# MAX3232.net
KiCad netlist of a schematic drawn in Altium Designer
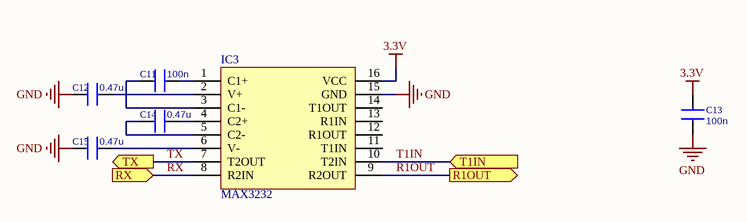
[diagram p0: MAX3232.SchDoc]

(export (version "E")
  (design (tool "Eeschema 10.0.6"))
  (components
    (comp (ref "C11")
      (value "100n")
      (footprint "C_0805")
      (description "Capacitor")
      (libsource (lib "AX_Altium_v2.3") (part "C0805"))
    )
    (comp (ref "C12")
      (value "0.47u")
      (footprint "C_0805")
      (description "Capacitor")
      (libsource (lib "AX_Altium_v2.3") (part "C0805"))
    )
    (comp (ref "C13")
      (value "100n")
      (footprint "C_0805")
      (description "Capacitor")
      (libsource (lib "AX_Altium_v2.3") (part "C0805"))
    )
    (comp (ref "C14")
      (value "0.47u")
      (footprint "C_0805")
      (description "Capacitor")
      (libsource (lib "AX_Altium_v2.3") (part "C0805"))
    )
    (comp (ref "C15")
      (value "0.47u")
      (footprint "C_0805")
      (description "Capacitor")
      (libsource (lib "AX_Altium_v2.3") (part "C0805"))
    )
    (comp (ref "IC3")
      (value "MAX3232")
      (footprint "SSOP-16")
      (description "RS-232 Line Driver/Receiver With ±15-kV ESD Protection")
      (libsource (lib "SmartOutletIntegratedLibrary") (part "MAX3232"))
    )
  )
  (nets
    (net (code "1") (name "/R1OUT") (class "Default")
      (node (ref "IC3") (pin "9") (pinfunction "R2OUT_9") (pintype "passive"))
    )
    (net (code "2") (name "/RX") (class "Default")
      (node (ref "IC3") (pin "8") (pinfunction "R2IN_8") (pintype "passive"))
    )
    (net (code "3") (name "/T1IN") (class "Default")
      (node (ref "IC3") (pin "10") (pinfunction "T2IN_10") (pintype "passive"))
    )
    (net (code "4") (name "/TX") (class "Default")
      (node (ref "IC3") (pin "7") (pinfunction "T2OUT_7") (pintype "passive"))
    )
    (net (code "5") (name "3.3V") (class "Default")
      (node (ref "C13") (pin "2") (pintype "passive"))
      (node (ref "IC3") (pin "16") (pinfunction "VCC_16") (pintype "passive"))
    )
    (net (code "6") (name "GND") (class "Default")
      (node (ref "C12") (pin "1") (pintype "passive"))
      (node (ref "C13") (pin "1") (pintype "passive"))
      (node (ref "C15") (pin "1") (pintype "passive"))
      (node (ref "IC3") (pin "15") (pinfunction "GND_15") (pintype "passive"))
    )
    (net (code "7") (name "Net-(IC3-C1+)") (class "Default")
      (node (ref "C11") (pin "2") (pintype "passive"))
      (node (ref "IC3") (pin "1") (pinfunction "C1+_1") (pintype "passive"))
    )
    (net (code "8") (name "Net-(IC3-C1-)") (class "Default")
      (node (ref "C11") (pin "1") (pintype "passive"))
      (node (ref "IC3") (pin "3") (pinfunction "C1-_3") (pintype "passive"))
    )
    (net (code "9") (name "Net-(IC3-C2+)") (class "Default")
      (node (ref "C14") (pin "2") (pintype "passive"))
      (node (ref "IC3") (pin "4") (pinfunction "C2+_4") (pintype "passive"))
    )
    (net (code "10") (name "Net-(IC3-C2-)") (class "Default")
      (node (ref "C14") (pin "1") (pintype "passive"))
      (node (ref "IC3") (pin "5") (pinfunction "C2-_5") (pintype "passive"))
    )
    (net (code "11") (name "Net-(IC3-V+)") (class "Default")
      (node (ref "C12") (pin "2") (pintype "passive"))
      (node (ref "IC3") (pin "2") (pinfunction "V+_2") (pintype "passive"))
    )
    (net (code "12") (name "Net-(IC3-V-)") (class "Default")
      (node (ref "C15") (pin "2") (pintype "passive"))
      (node (ref "IC3") (pin "6") (pinfunction "V-_6") (pintype "passive"))
    )
    (net (code "13") (name "unconnected-(IC3-R1IN-Pad13)") (class "Default")
      (node (ref "IC3") (pin "13") (pinfunction "R1IN_13") (pintype "passive"))
    )
    (net (code "14") (name "unconnected-(IC3-R1OUT-Pad12)") (class "Default")
      (node (ref "IC3") (pin "12") (pinfunction "R1OUT_12") (pintype "passive"))
    )
    (net (code "15") (name "unconnected-(IC3-T1IN-Pad11)") (class "Default")
      (node (ref "IC3") (pin "11") (pinfunction "T1IN_11") (pintype "passive"))
    )
    (net (code "16") (name "unconnected-(IC3-T1OUT-Pad14)") (class "Default")
      (node (ref "IC3") (pin "14") (pinfunction "T1OUT_14") (pintype "passive"))
    )
  )
)
